# ProPrj.net
KiCad netlist of a schematic drawn in EasyEDA Pro
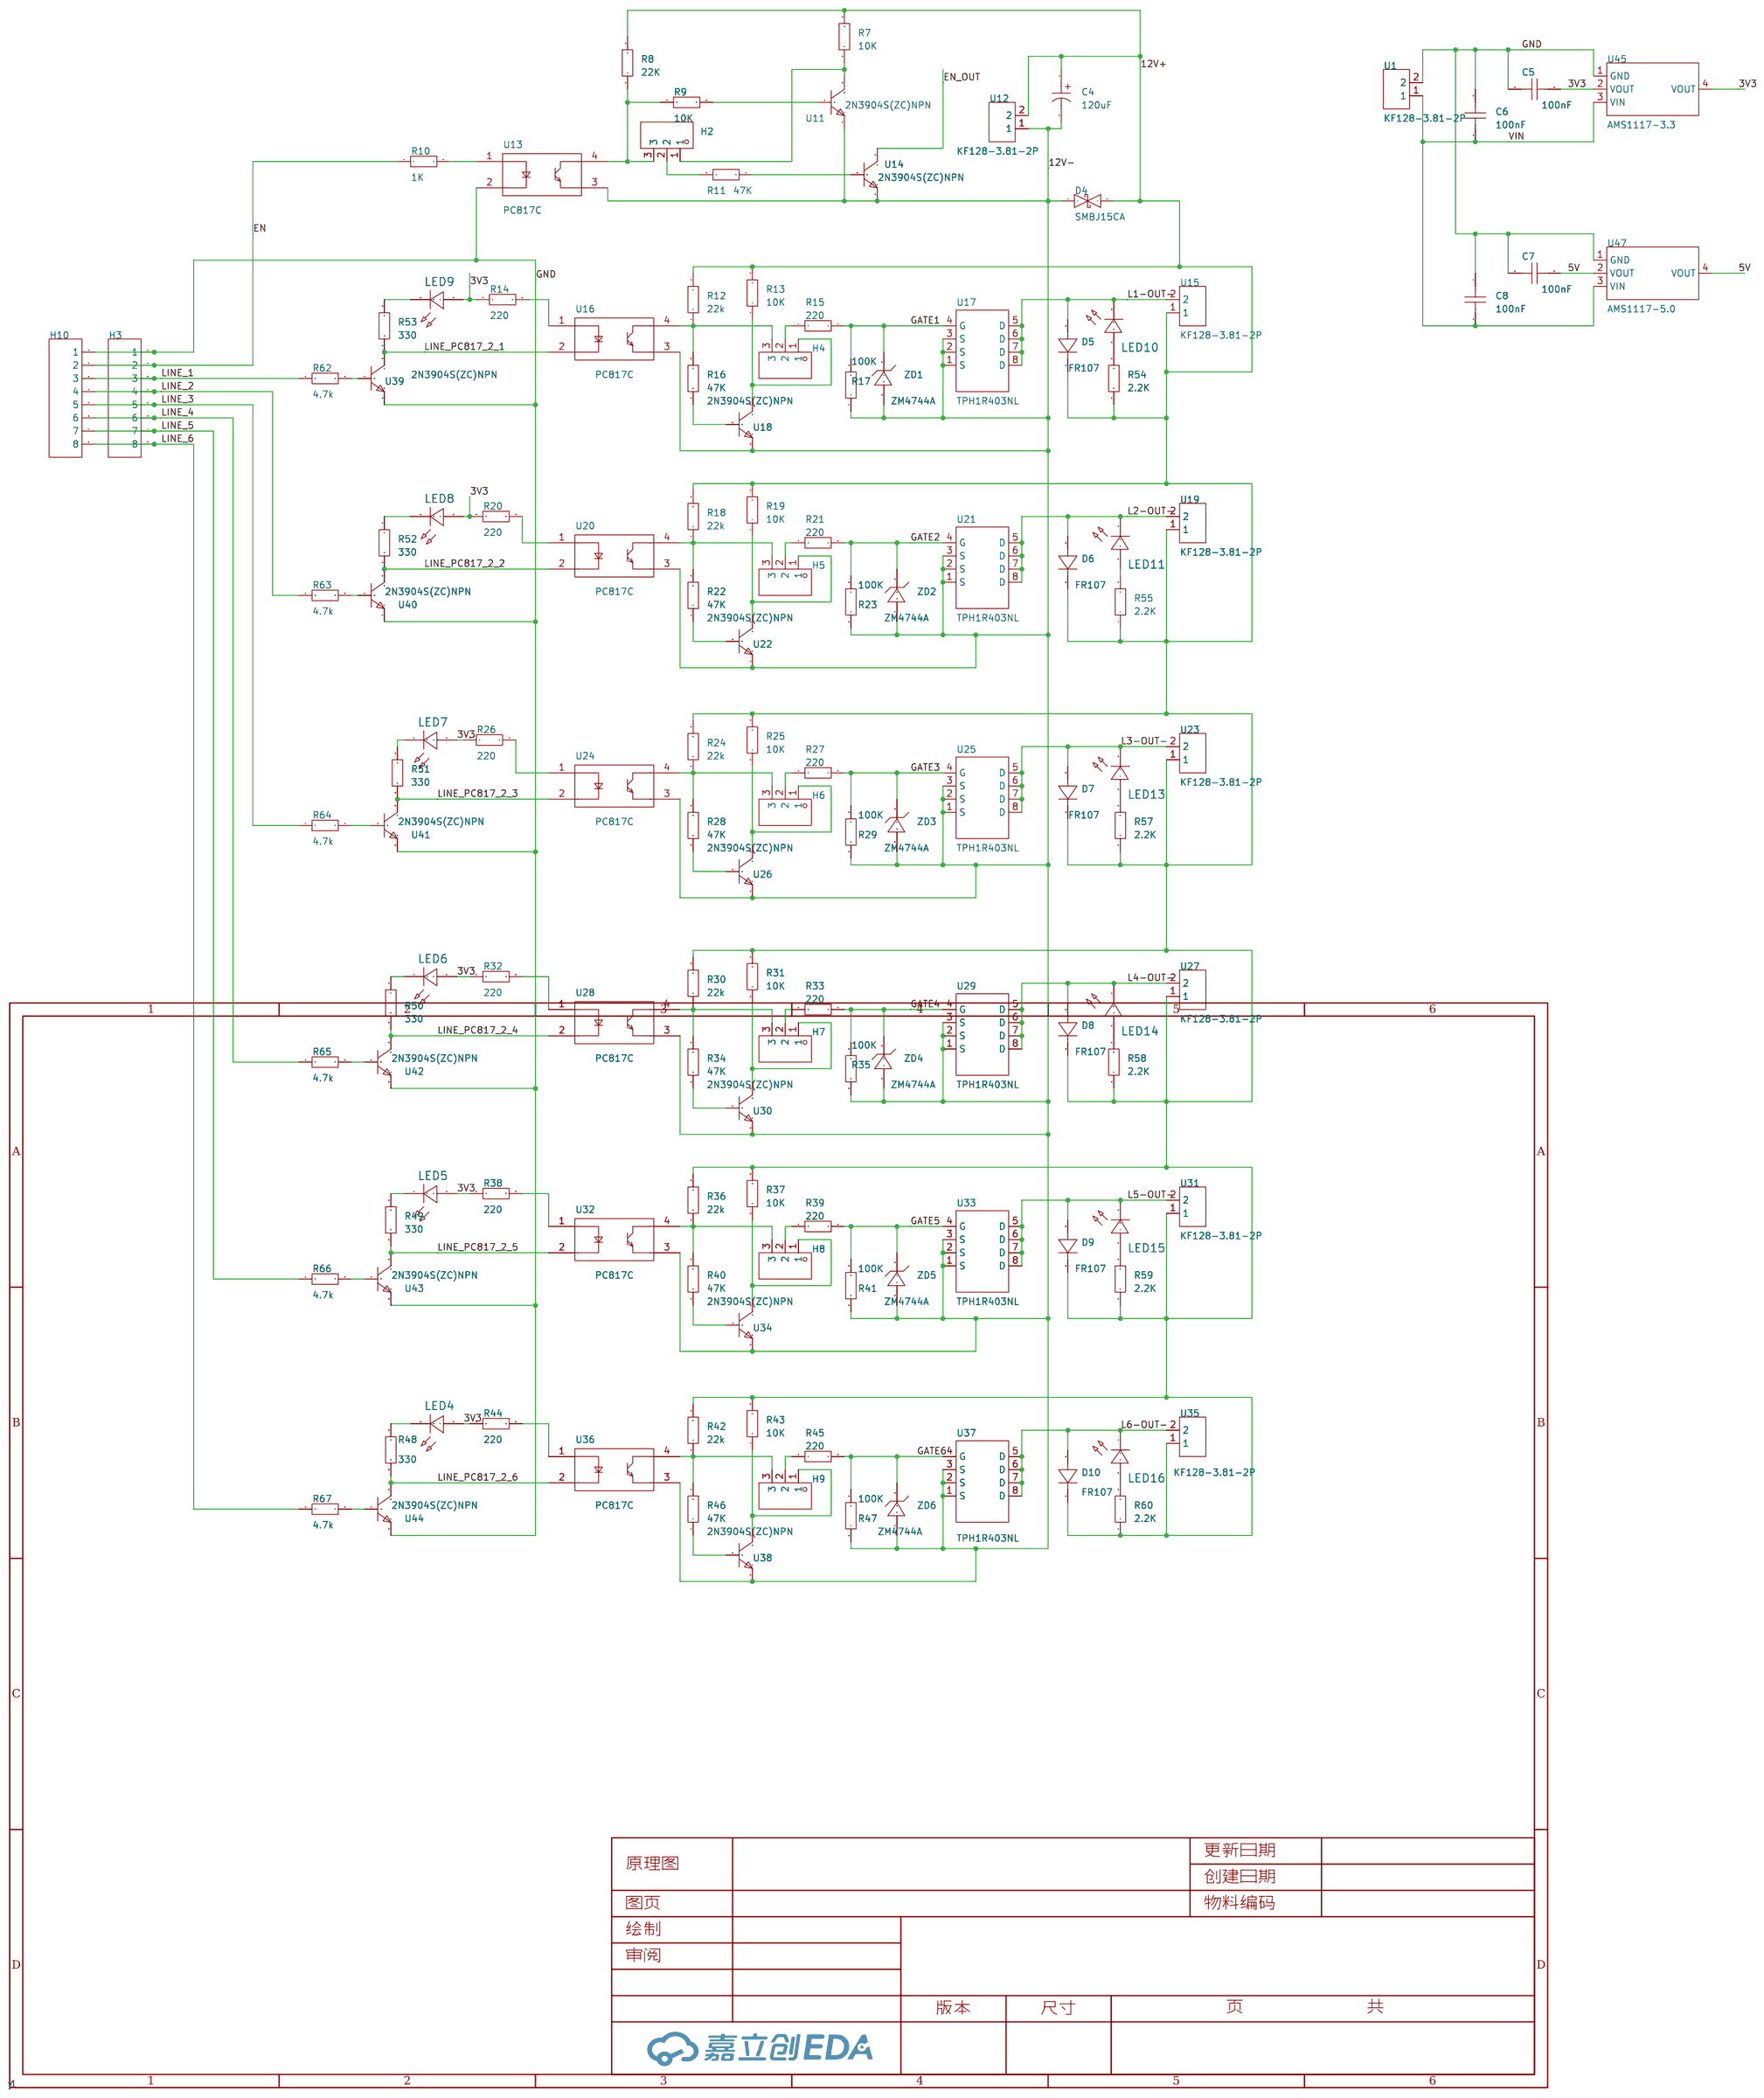
[diagram p0: 光耦隔离输出]
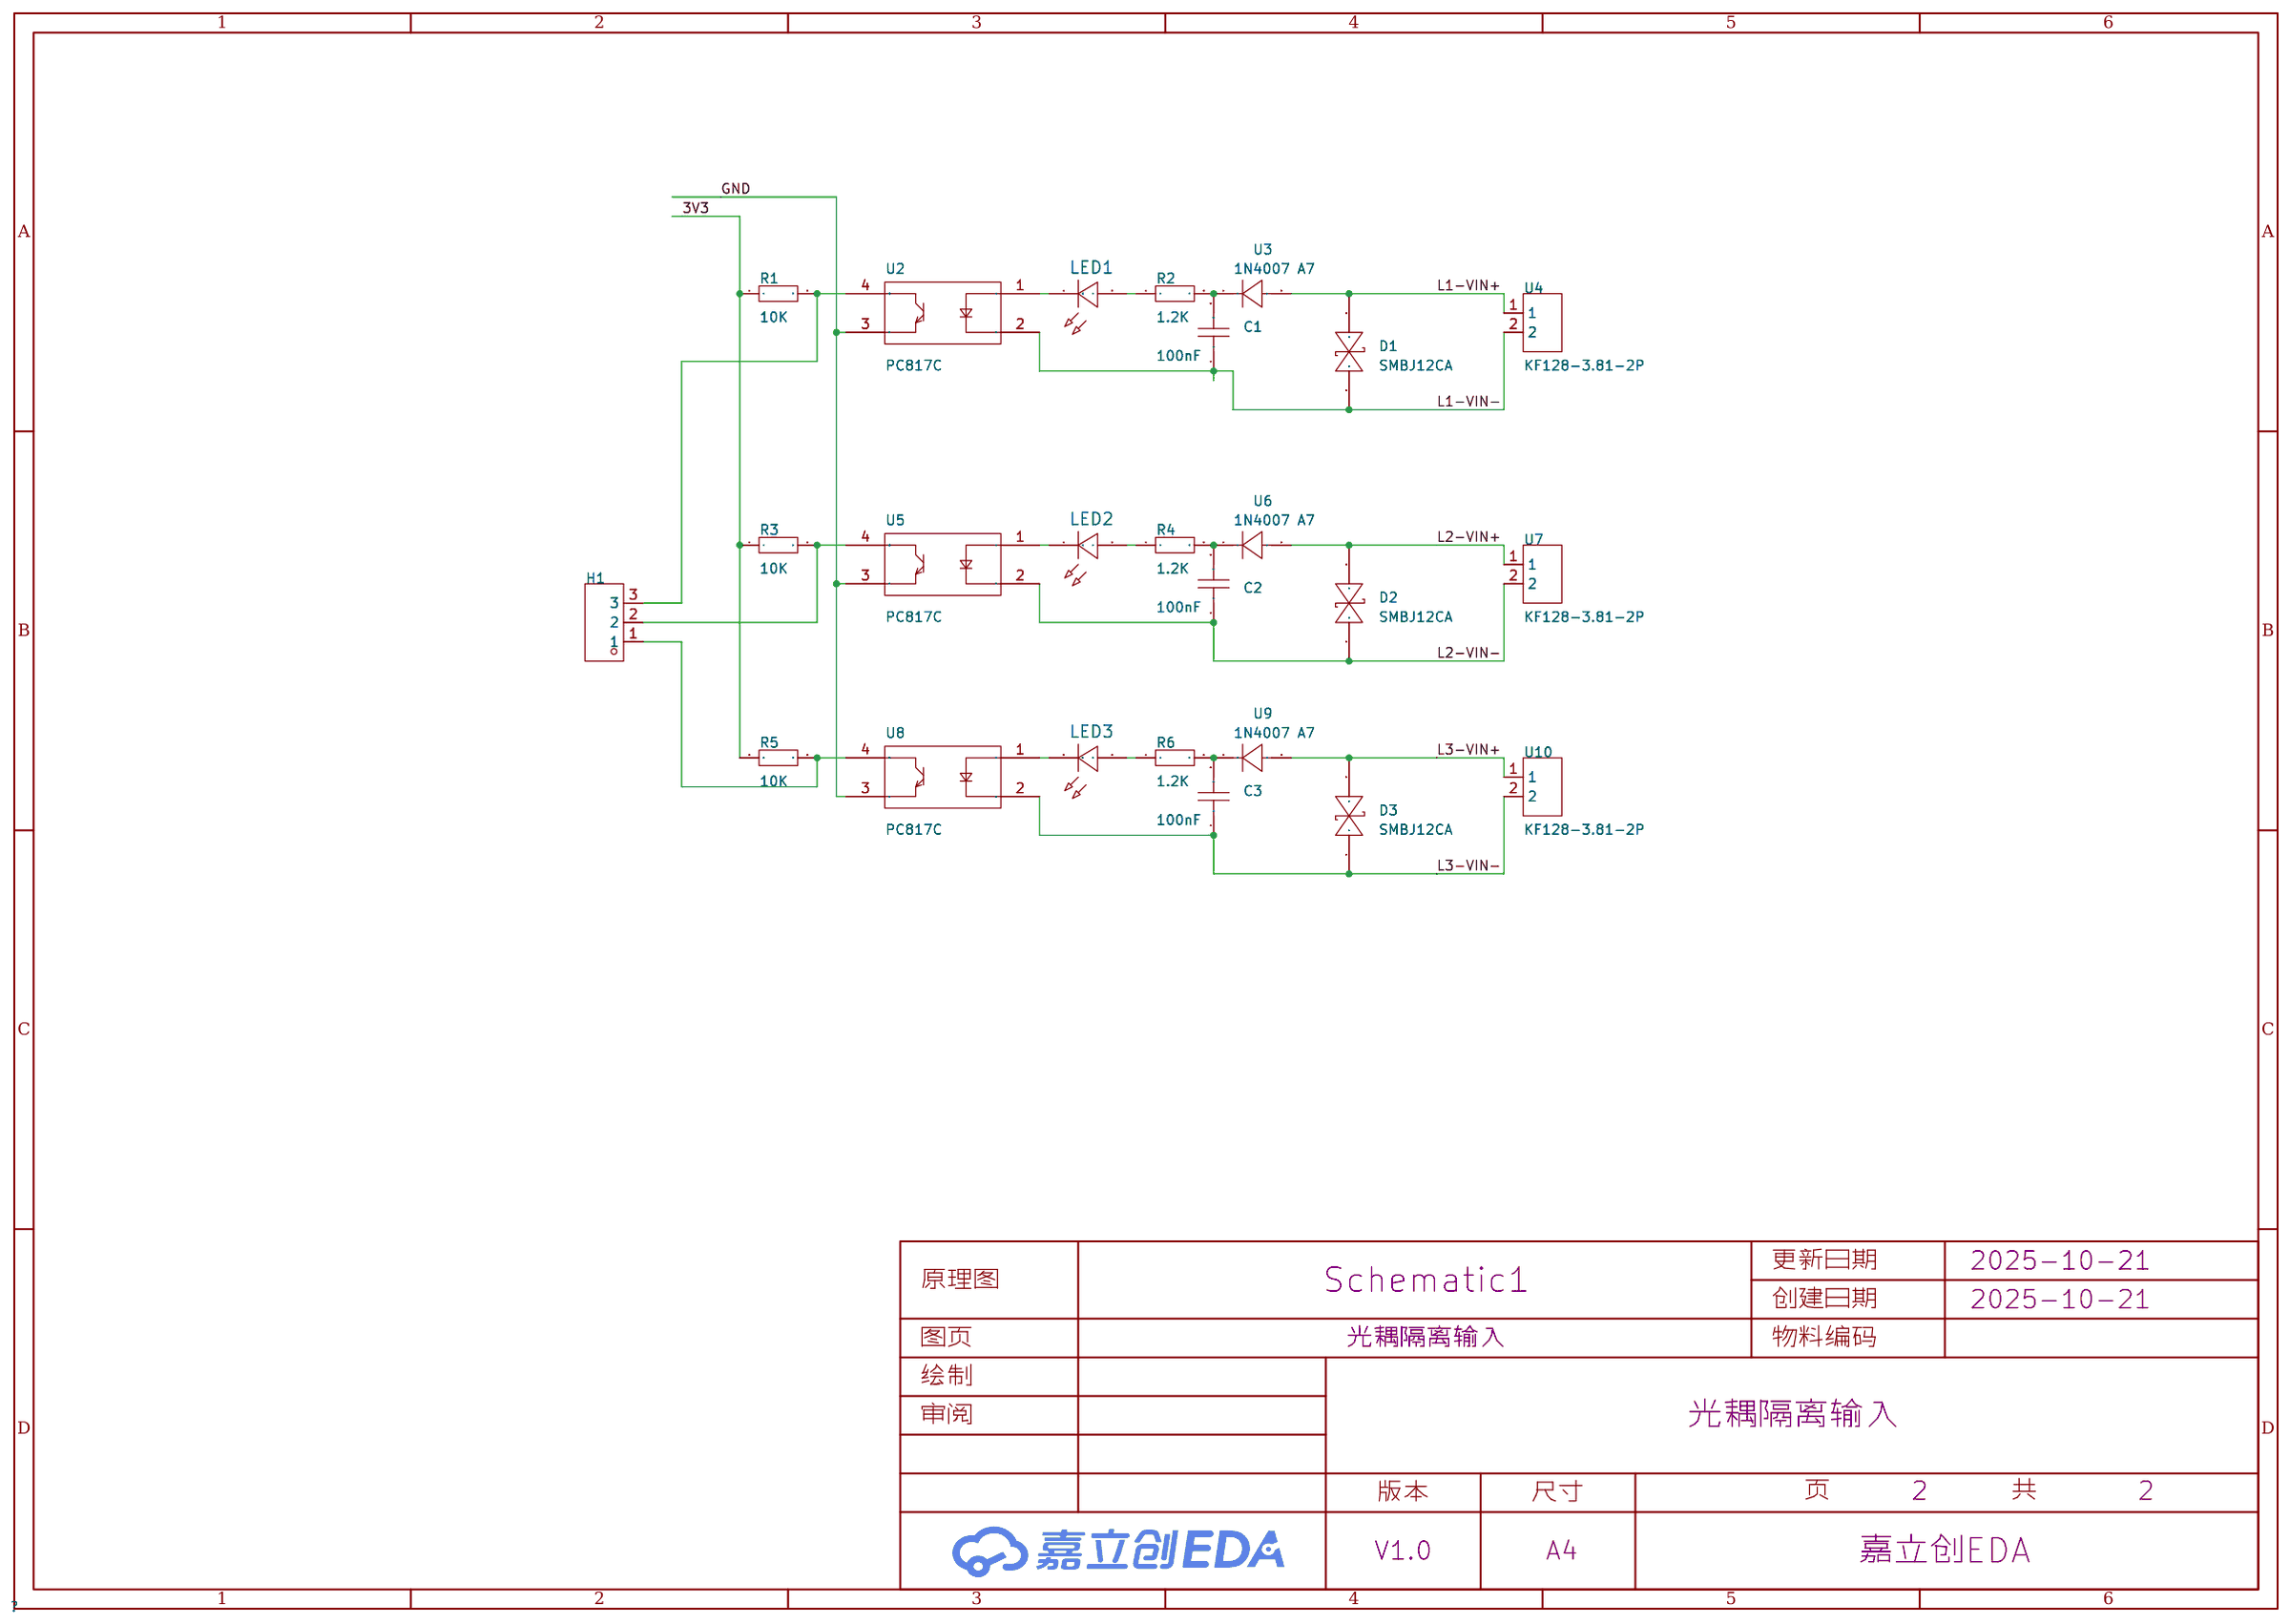
[diagram p1: 光耦隔离输入]

(export (version "E")
  (design (tool "Eeschema 10.0.6"))
  (components
    (comp (ref "C4")
      (value "120uF")
      (footprint "easyedapro:CAP-TH_BD6.3-P2.50-D0.5-FD")
      (description "容值:120uF;精度:±20%;额定电压:35V;纹波电流:550mA@100kHz;等效串联电阻(ESR):150mΩ@100kHz;")
      (fields
        (field (name "Manufacturer Part") "DHG035M127E090S1AA")
        (field (name "Manufacturer") "KNSCHA(科尼盛)")
      )
      (libsource (lib "easyedapro") (part "DHG035M127E090S1AA"))
    )
    (comp (ref "C5")
      (value "100nF")
      (footprint "easyedapro:C0603")
      (libsource (lib "easyedapro") (part "CapAcitance"))
    )
    (comp (ref "C6")
      (value "100nF")
      (footprint "easyedapro:C0603")
      (libsource (lib "easyedapro") (part "CapAcitance"))
    )
    (comp (ref "C7")
      (value "100nF")
      (footprint "easyedapro:C0603")
      (libsource (lib "easyedapro") (part "CapAcitance"))
    )
    (comp (ref "C8")
      (value "100nF")
      (footprint "easyedapro:C0603")
      (libsource (lib "easyedapro") (part "CapAcitance"))
    )
    (comp (ref "D4")
      (value "SMBJ15CA")
      (footprint "easyedapro:SMB_L4.6-W3.6-LS5.3-BI")
      (description "反向截止电压(Vrwm):15V;钳位电压:24.4V;峰值脉冲电流(Ipp):24.6A;击穿电压:16.7V;")
      (fields (field (name "Manufacturer") "JJW(捷捷微)"))
      (libsource (lib "easyedapro") (part "SMBJ15CA_C330064"))
    )
    (comp (ref "D5")
      (value "FR107")
      (footprint "easyedapro:SOD-123_L2.8-W1.8-LS3.7-RD")
      (description "二极管配置:-;正向压降(Vf):1.3V@1A;直流反向耐压(Vr):1kV;整流电流:1A;反向恢复时间(Trr):500ns;")
      (fields (field (name "Manufacturer") "JSMSEMI(杰盛微)"))
      (libsource (lib "easyedapro") (part "FR107_C963379"))
    )
    (comp (ref "D6")
      (value "FR107")
      (footprint "easyedapro:SOD-123_L2.8-W1.8-LS3.7-RD")
      (description "二极管配置:-;正向压降(Vf):1.3V@1A;直流反向耐压(Vr):1kV;整流电流:1A;反向恢复时间(Trr):500ns;")
      (fields (field (name "Manufacturer") "JSMSEMI(杰盛微)"))
      (libsource (lib "easyedapro") (part "FR107_C963379"))
    )
    (comp (ref "D7")
      (value "FR107")
      (footprint "easyedapro:SOD-123_L2.8-W1.8-LS3.7-RD")
      (description "二极管配置:-;正向压降(Vf):1.3V@1A;直流反向耐压(Vr):1kV;整流电流:1A;反向恢复时间(Trr):500ns;")
      (fields (field (name "Manufacturer") "JSMSEMI(杰盛微)"))
      (libsource (lib "easyedapro") (part "FR107_C963379"))
    )
    (comp (ref "D8")
      (value "FR107")
      (footprint "easyedapro:SOD-123_L2.8-W1.8-LS3.7-RD")
      (description "二极管配置:-;正向压降(Vf):1.3V@1A;直流反向耐压(Vr):1kV;整流电流:1A;反向恢复时间(Trr):500ns;")
      (fields (field (name "Manufacturer") "JSMSEMI(杰盛微)"))
      (libsource (lib "easyedapro") (part "FR107_C963379"))
    )
    (comp (ref "D9")
      (value "FR107")
      (footprint "easyedapro:SOD-123_L2.8-W1.8-LS3.7-RD")
      (description "二极管配置:-;正向压降(Vf):1.3V@1A;直流反向耐压(Vr):1kV;整流电流:1A;反向恢复时间(Trr):500ns;")
      (fields (field (name "Manufacturer") "JSMSEMI(杰盛微)"))
      (libsource (lib "easyedapro") (part "FR107_C963379"))
    )
    (comp (ref "D10")
      (value "FR107")
      (footprint "easyedapro:SOD-123_L2.8-W1.8-LS3.7-RD")
      (description "二极管配置:-;正向压降(Vf):1.3V@1A;直流反向耐压(Vr):1kV;整流电流:1A;反向恢复时间(Trr):500ns;")
      (fields (field (name "Manufacturer") "JSMSEMI(杰盛微)"))
      (libsource (lib "easyedapro") (part "FR107_C963379"))
    )
    (comp (ref "H2")
      (value "~")
      (footprint "easyedapro:HDR-TH_3P-P2.54-V-M")
      (libsource (lib "easyedapro") (part "HDR-M_2.54_1x3P"))
    )
    (comp (ref "H3")
      (value "~")
      (footprint "easyedapro:HDR-TH_8P-P2.54-V-M")
      (libsource (lib "easyedapro") (part "Header-Male-2.54_1x8"))
    )
    (comp (ref "H4")
      (value "~")
      (footprint "easyedapro:HDR-TH_3P-P2.54-V-M")
      (libsource (lib "easyedapro") (part "HDR-M_2.54_1x3P"))
    )
    (comp (ref "H5")
      (value "~")
      (footprint "easyedapro:HDR-TH_3P-P2.54-V-M")
      (libsource (lib "easyedapro") (part "HDR-M_2.54_1x3P"))
    )
    (comp (ref "H6")
      (value "~")
      (footprint "easyedapro:HDR-TH_3P-P2.54-V-M")
      (libsource (lib "easyedapro") (part "HDR-M_2.54_1x3P"))
    )
    (comp (ref "H7")
      (value "~")
      (footprint "easyedapro:HDR-TH_3P-P2.54-V-M")
      (libsource (lib "easyedapro") (part "HDR-M_2.54_1x3P"))
    )
    (comp (ref "H8")
      (value "~")
      (footprint "easyedapro:HDR-TH_3P-P2.54-V-M")
      (libsource (lib "easyedapro") (part "HDR-M_2.54_1x3P"))
    )
    (comp (ref "H9")
      (value "~")
      (footprint "easyedapro:HDR-TH_3P-P2.54-V-M")
      (libsource (lib "easyedapro") (part "HDR-M_2.54_1x3P"))
    )
    (comp (ref "H10")
      (value "~")
      (footprint "easyedapro:HDR-TH_8P-P2.54-V-M")
      (libsource (lib "easyedapro") (part "Header-Male-2.54_1x8"))
    )
    (comp (ref "LED4")
      (value "~")
      (footprint "easyedapro:LED_0603")
      (libsource (lib "easyedapro") (part "LED_R"))
    )
    (comp (ref "LED5")
      (value "~")
      (footprint "easyedapro:LED_0603")
      (libsource (lib "easyedapro") (part "LED_R"))
    )
    (comp (ref "LED6")
      (value "~")
      (footprint "easyedapro:LED_0603")
      (libsource (lib "easyedapro") (part "LED_R"))
    )
    (comp (ref "LED7")
      (value "~")
      (footprint "easyedapro:LED_0603")
      (libsource (lib "easyedapro") (part "LED_R"))
    )
    (comp (ref "LED8")
      (value "~")
      (footprint "easyedapro:LED_0603")
      (libsource (lib "easyedapro") (part "LED_R"))
    )
    (comp (ref "LED9")
      (value "~")
      (footprint "easyedapro:LED_0603")
      (libsource (lib "easyedapro") (part "LED_R"))
    )
    (comp (ref "LED10")
      (value "~")
      (footprint "easyedapro:LED_0603")
      (libsource (lib "easyedapro") (part "LED_R"))
    )
    (comp (ref "LED11")
      (value "~")
      (footprint "easyedapro:LED_0603")
      (libsource (lib "easyedapro") (part "LED_R"))
    )
    (comp (ref "LED13")
      (value "~")
      (footprint "easyedapro:LED_0603")
      (libsource (lib "easyedapro") (part "LED_R"))
    )
    (comp (ref "LED14")
      (value "~")
      (footprint "easyedapro:LED_0603")
      (libsource (lib "easyedapro") (part "LED_R"))
    )
    (comp (ref "LED15")
      (value "~")
      (footprint "easyedapro:LED_0603")
      (libsource (lib "easyedapro") (part "LED_R"))
    )
    (comp (ref "LED16")
      (value "~")
      (footprint "easyedapro:LED_0603")
      (libsource (lib "easyedapro") (part "LED_R"))
    )
    (comp (ref "R7") (value "10K") (footprint "easyedapro:R0603") (libsource (lib "easyedapro") (part "电阻")))
    (comp (ref "R8") (value "22K") (footprint "easyedapro:R0603") (libsource (lib "easyedapro") (part "电阻")))
    (comp (ref "R9") (value "10K") (footprint "easyedapro:R0603") (libsource (lib "easyedapro") (part "电阻")))
    (comp (ref "R10") (value "1K") (footprint "easyedapro:R0603") (libsource (lib "easyedapro") (part "电阻")))
    (comp (ref "R11") (value "47K") (footprint "easyedapro:R0603") (libsource (lib "easyedapro") (part "电阻")))
    (comp (ref "R12") (value "22k") (footprint "easyedapro:R0603") (libsource (lib "easyedapro") (part "电阻")))
    (comp (ref "R13") (value "10K") (footprint "easyedapro:R0603") (libsource (lib "easyedapro") (part "电阻")))
    (comp (ref "R14") (value "220") (footprint "easyedapro:R0603") (libsource (lib "easyedapro") (part "电阻")))
    (comp (ref "R15") (value "220") (footprint "easyedapro:R0603") (libsource (lib "easyedapro") (part "电阻")))
    (comp (ref "R16") (value "47K") (footprint "easyedapro:R0603") (libsource (lib "easyedapro") (part "电阻")))
    (comp (ref "R17")
      (value "100K")
      (footprint "easyedapro:R0603")
      (libsource (lib "easyedapro") (part "电阻"))
    )
    (comp (ref "R18") (value "22k") (footprint "easyedapro:R0603") (libsource (lib "easyedapro") (part "电阻")))
    (comp (ref "R19") (value "10K") (footprint "easyedapro:R0603") (libsource (lib "easyedapro") (part "电阻")))
    (comp (ref "R20") (value "220") (footprint "easyedapro:R0603") (libsource (lib "easyedapro") (part "电阻")))
    (comp (ref "R21") (value "220") (footprint "easyedapro:R0603") (libsource (lib "easyedapro") (part "电阻")))
    (comp (ref "R22") (value "47K") (footprint "easyedapro:R0603") (libsource (lib "easyedapro") (part "电阻")))
    (comp (ref "R23")
      (value "100K")
      (footprint "easyedapro:R0603")
      (libsource (lib "easyedapro") (part "电阻"))
    )
    (comp (ref "R24") (value "22k") (footprint "easyedapro:R0603") (libsource (lib "easyedapro") (part "电阻")))
    (comp (ref "R25") (value "10K") (footprint "easyedapro:R0603") (libsource (lib "easyedapro") (part "电阻")))
    (comp (ref "R26") (value "220") (footprint "easyedapro:R0603") (libsource (lib "easyedapro") (part "电阻")))
    (comp (ref "R27") (value "220") (footprint "easyedapro:R0603") (libsource (lib "easyedapro") (part "电阻")))
    (comp (ref "R28") (value "47K") (footprint "easyedapro:R0603") (libsource (lib "easyedapro") (part "电阻")))
    (comp (ref "R29")
      (value "100K")
      (footprint "easyedapro:R0603")
      (libsource (lib "easyedapro") (part "电阻"))
    )
    (comp (ref "R30") (value "22k") (footprint "easyedapro:R0603") (libsource (lib "easyedapro") (part "电阻")))
    (comp (ref "R31") (value "10K") (footprint "easyedapro:R0603") (libsource (lib "easyedapro") (part "电阻")))
    (comp (ref "R32") (value "220") (footprint "easyedapro:R0603") (libsource (lib "easyedapro") (part "电阻")))
    (comp (ref "R33") (value "220") (footprint "easyedapro:R0603") (libsource (lib "easyedapro") (part "电阻")))
    (comp (ref "R34") (value "47K") (footprint "easyedapro:R0603") (libsource (lib "easyedapro") (part "电阻")))
    (comp (ref "R35")
      (value "100K")
      (footprint "easyedapro:R0603")
      (libsource (lib "easyedapro") (part "电阻"))
    )
    (comp (ref "R36") (value "22k") (footprint "easyedapro:R0603") (libsource (lib "easyedapro") (part "电阻")))
    (comp (ref "R37") (value "10K") (footprint "easyedapro:R0603") (libsource (lib "easyedapro") (part "电阻")))
    (comp (ref "R38") (value "220") (footprint "easyedapro:R0603") (libsource (lib "easyedapro") (part "电阻")))
    (comp (ref "R39") (value "220") (footprint "easyedapro:R0603") (libsource (lib "easyedapro") (part "电阻")))
    (comp (ref "R40") (value "47K") (footprint "easyedapro:R0603") (libsource (lib "easyedapro") (part "电阻")))
    (comp (ref "R41")
      (value "100K")
      (footprint "easyedapro:R0603")
      (libsource (lib "easyedapro") (part "电阻"))
    )
    (comp (ref "R42") (value "22k") (footprint "easyedapro:R0603") (libsource (lib "easyedapro") (part "电阻")))
    (comp (ref "R43") (value "10K") (footprint "easyedapro:R0603") (libsource (lib "easyedapro") (part "电阻")))
    (comp (ref "R44") (value "220") (footprint "easyedapro:R0603") (libsource (lib "easyedapro") (part "电阻")))
    (comp (ref "R45") (value "220") (footprint "easyedapro:R0603") (libsource (lib "easyedapro") (part "电阻")))
    (comp (ref "R46") (value "47K") (footprint "easyedapro:R0603") (libsource (lib "easyedapro") (part "电阻")))
    (comp (ref "R47")
      (value "100K")
      (footprint "easyedapro:R0603")
      (libsource (lib "easyedapro") (part "电阻"))
    )
    (comp (ref "R48") (value "330") (footprint "easyedapro:R0603") (libsource (lib "easyedapro") (part "电阻")))
    (comp (ref "R49") (value "330") (footprint "easyedapro:R0603") (libsource (lib "easyedapro") (part "电阻")))
    (comp (ref "R50") (value "330") (footprint "easyedapro:R0603") (libsource (lib "easyedapro") (part "电阻")))
    (comp (ref "R51") (value "330") (footprint "easyedapro:R0603") (libsource (lib "easyedapro") (part "电阻")))
    (comp (ref "R52") (value "330") (footprint "easyedapro:R0603") (libsource (lib "easyedapro") (part "电阻")))
    (comp (ref "R53") (value "330") (footprint "easyedapro:R0603") (libsource (lib "easyedapro") (part "电阻")))
    (comp (ref "R54")
      (value "2.2K")
      (footprint "easyedapro:R0603")
      (libsource (lib "easyedapro") (part "电阻"))
    )
    (comp (ref "R55")
      (value "2.2K")
      (footprint "easyedapro:R0603")
      (libsource (lib "easyedapro") (part "电阻"))
    )
    (comp (ref "R57")
      (value "2.2K")
      (footprint "easyedapro:R0603")
      (libsource (lib "easyedapro") (part "电阻"))
    )
    (comp (ref "R58")
      (value "2.2K")
      (footprint "easyedapro:R0603")
      (libsource (lib "easyedapro") (part "电阻"))
    )
    (comp (ref "R59")
      (value "2.2K")
      (footprint "easyedapro:R0603")
      (libsource (lib "easyedapro") (part "电阻"))
    )
    (comp (ref "R60")
      (value "2.2K")
      (footprint "easyedapro:R0603")
      (libsource (lib "easyedapro") (part "电阻"))
    )
    (comp (ref "R62")
      (value "4.7k")
      (footprint "easyedapro:R0603")
      (libsource (lib "easyedapro") (part "电阻"))
    )
    (comp (ref "R63")
      (value "4.7k")
      (footprint "easyedapro:R0603")
      (libsource (lib "easyedapro") (part "电阻"))
    )
    (comp (ref "R64")
      (value "4.7k")
      (footprint "easyedapro:R0603")
      (libsource (lib "easyedapro") (part "电阻"))
    )
    (comp (ref "R65")
      (value "4.7k")
      (footprint "easyedapro:R0603")
      (libsource (lib "easyedapro") (part "电阻"))
    )
    (comp (ref "R66")
      (value "4.7k")
      (footprint "easyedapro:R0603")
      (libsource (lib "easyedapro") (part "电阻"))
    )
    (comp (ref "R67")
      (value "4.7k")
      (footprint "easyedapro:R0603")
      (libsource (lib "easyedapro") (part "电阻"))
    )
    (comp (ref "U1")
      (value "KF128-3.81-2P")
      (footprint "easyedapro:CONN-TH_2P-P3.81_KF128-3.81-2P")
      (libsource (lib "easyedapro") (part "KF128-3.81-2P_C9900030554"))
    )
    (comp (ref "U11")
      (value "2N3904S(ZC)NPN")
      (footprint "easyedapro:SOT-23-3_L2.9-W1.3-P0.95-LS2.4-BR")
      (libsource (lib "easyedapro") (part "2N3904S(ZC)NPN"))
    )
    (comp (ref "U12")
      (value "KF128-3.81-2P")
      (footprint "easyedapro:CONN-TH_2P-P3.81_KF128-3.81-2P")
      (libsource (lib "easyedapro") (part "KF128-3.81-2P_C9900030554"))
    )
    (comp (ref "U13")
      (value "PC817C")
      (footprint "easyedapro:DIP-4_L4.6-W6.5-P2.54-LS7.6-BL")
      (fields (field (name "Manufacturer") "GOODWORK(固得沃克)"))
      (libsource (lib "easyedapro") (part "PC817-4"))
    )
    (comp (ref "U14")
      (value "2N3904S(ZC)NPN")
      (footprint "easyedapro:SOT-23-3_L2.9-W1.3-P0.95-LS2.4-BR")
      (libsource (lib "easyedapro") (part "2N3904S(ZC)NPN"))
    )
    (comp (ref "U15")
      (value "KF128-3.81-2P")
      (footprint "easyedapro:CONN-TH_2P-P3.81_KF128-3.81-2P")
      (libsource (lib "easyedapro") (part "KF128-3.81-2P_C9900030554"))
    )
    (comp (ref "U16")
      (value "PC817C")
      (footprint "easyedapro:DIP-4_L4.6-W6.5-P2.54-LS7.6-BL")
      (fields (field (name "Manufacturer") "GOODWORK(固得沃克)"))
      (libsource (lib "easyedapro") (part "PC817-4"))
    )
    (comp (ref "U17")
      (value "TPH1R403NL")
      (footprint "easyedapro:DFN-8_L5.0-W5.0-P1.27-LS6.0-EP")
      (libsource (lib "easyedapro") (part "TPH1R403NL_C9900016373"))
    )
    (comp (ref "U18")
      (value "2N3904S(ZC)NPN")
      (footprint "easyedapro:SOT-23-3_L2.9-W1.3-P0.95-LS2.4-BR")
      (libsource (lib "easyedapro") (part "2N3904S(ZC)NPN"))
    )
    (comp (ref "U19")
      (value "KF128-3.81-2P")
      (footprint "easyedapro:CONN-TH_2P-P3.81_KF128-3.81-2P")
      (libsource (lib "easyedapro") (part "KF128-3.81-2P_C9900030554"))
    )
    (comp (ref "U20")
      (value "PC817C")
      (footprint "easyedapro:DIP-4_L4.6-W6.5-P2.54-LS7.6-BL")
      (fields (field (name "Manufacturer") "GOODWORK(固得沃克)"))
      (libsource (lib "easyedapro") (part "PC817-4"))
    )
    (comp (ref "U21")
      (value "TPH1R403NL")
      (footprint "easyedapro:DFN-8_L5.0-W5.0-P1.27-LS6.0-EP")
      (libsource (lib "easyedapro") (part "TPH1R403NL_C9900016373"))
    )
    (comp (ref "U22")
      (value "2N3904S(ZC)NPN")
      (footprint "easyedapro:SOT-23-3_L2.9-W1.3-P0.95-LS2.4-BR")
      (libsource (lib "easyedapro") (part "2N3904S(ZC)NPN"))
    )
    (comp (ref "U23")
      (value "KF128-3.81-2P")
      (footprint "easyedapro:CONN-TH_2P-P3.81_KF128-3.81-2P")
      (libsource (lib "easyedapro") (part "KF128-3.81-2P_C9900030554"))
    )
    (comp (ref "U24")
      (value "PC817C")
      (footprint "easyedapro:DIP-4_L4.6-W6.5-P2.54-LS7.6-BL")
      (fields (field (name "Manufacturer") "GOODWORK(固得沃克)"))
      (libsource (lib "easyedapro") (part "PC817-4"))
    )
    (comp (ref "U25")
      (value "TPH1R403NL")
      (footprint "easyedapro:DFN-8_L5.0-W5.0-P1.27-LS6.0-EP")
      (libsource (lib "easyedapro") (part "TPH1R403NL_C9900016373"))
    )
    (comp (ref "U26")
      (value "2N3904S(ZC)NPN")
      (footprint "easyedapro:SOT-23-3_L2.9-W1.3-P0.95-LS2.4-BR")
      (libsource (lib "easyedapro") (part "2N3904S(ZC)NPN"))
    )
    (comp (ref "U27")
      (value "KF128-3.81-2P")
      (footprint "easyedapro:CONN-TH_2P-P3.81_KF128-3.81-2P")
      (libsource (lib "easyedapro") (part "KF128-3.81-2P_C9900030554"))
    )
    (comp (ref "U28")
      (value "PC817C")
      (footprint "easyedapro:DIP-4_L4.6-W6.5-P2.54-LS7.6-BL")
      (fields (field (name "Manufacturer") "GOODWORK(固得沃克)"))
      (libsource (lib "easyedapro") (part "PC817-4"))
    )
    (comp (ref "U29")
      (value "TPH1R403NL")
      (footprint "easyedapro:DFN-8_L5.0-W5.0-P1.27-LS6.0-EP")
      (libsource (lib "easyedapro") (part "TPH1R403NL_C9900016373"))
    )
    (comp (ref "U30")
      (value "2N3904S(ZC)NPN")
      (footprint "easyedapro:SOT-23-3_L2.9-W1.3-P0.95-LS2.4-BR")
      (libsource (lib "easyedapro") (part "2N3904S(ZC)NPN"))
    )
    (comp (ref "U31")
      (value "KF128-3.81-2P")
      (footprint "easyedapro:CONN-TH_2P-P3.81_KF128-3.81-2P")
      (libsource (lib "easyedapro") (part "KF128-3.81-2P_C9900030554"))
    )
    (comp (ref "U32")
      (value "PC817C")
      (footprint "easyedapro:DIP-4_L4.6-W6.5-P2.54-LS7.6-BL")
      (fields (field (name "Manufacturer") "GOODWORK(固得沃克)"))
      (libsource (lib "easyedapro") (part "PC817-4"))
    )
    (comp (ref "U33")
      (value "TPH1R403NL")
      (footprint "easyedapro:DFN-8_L5.0-W5.0-P1.27-LS6.0-EP")
      (libsource (lib "easyedapro") (part "TPH1R403NL_C9900016373"))
    )
    (comp (ref "U34")
      (value "2N3904S(ZC)NPN")
      (footprint "easyedapro:SOT-23-3_L2.9-W1.3-P0.95-LS2.4-BR")
      (libsource (lib "easyedapro") (part "2N3904S(ZC)NPN"))
    )
    (comp (ref "U35")
      (value "KF128-3.81-2P")
      (footprint "easyedapro:CONN-TH_2P-P3.81_KF128-3.81-2P")
      (libsource (lib "easyedapro") (part "KF128-3.81-2P_C9900030554"))
    )
    (comp (ref "U36")
      (value "PC817C")
      (footprint "easyedapro:DIP-4_L4.6-W6.5-P2.54-LS7.6-BL")
      (fields (field (name "Manufacturer") "GOODWORK(固得沃克)"))
      (libsource (lib "easyedapro") (part "PC817-4"))
    )
    (comp (ref "U37")
      (value "TPH1R403NL")
      (footprint "easyedapro:DFN-8_L5.0-W5.0-P1.27-LS6.0-EP")
      (libsource (lib "easyedapro") (part "TPH1R403NL_C9900016373"))
    )
    (comp (ref "U38")
      (value "2N3904S(ZC)NPN")
      (footprint "easyedapro:SOT-23-3_L2.9-W1.3-P0.95-LS2.4-BR")
      (libsource (lib "easyedapro") (part "2N3904S(ZC)NPN"))
    )
    (comp (ref "U39")
      (value "2N3904S(ZC)NPN")
      (footprint "easyedapro:SOT-23-3_L2.9-W1.3-P0.95-LS2.4-BR")
      (libsource (lib "easyedapro") (part "2N3904S(ZC)NPN"))
    )
    (comp (ref "U40")
      (value "2N3904S(ZC)NPN")
      (footprint "easyedapro:SOT-23-3_L2.9-W1.3-P0.95-LS2.4-BR")
      (libsource (lib "easyedapro") (part "2N3904S(ZC)NPN"))
    )
    (comp (ref "U41")
      (value "2N3904S(ZC)NPN")
      (footprint "easyedapro:SOT-23-3_L2.9-W1.3-P0.95-LS2.4-BR")
      (libsource (lib "easyedapro") (part "2N3904S(ZC)NPN"))
    )
    (comp (ref "U42")
      (value "2N3904S(ZC)NPN")
      (footprint "easyedapro:SOT-23-3_L2.9-W1.3-P0.95-LS2.4-BR")
      (libsource (lib "easyedapro") (part "2N3904S(ZC)NPN"))
    )
    (comp (ref "U43")
      (value "2N3904S(ZC)NPN")
      (footprint "easyedapro:SOT-23-3_L2.9-W1.3-P0.95-LS2.4-BR")
      (libsource (lib "easyedapro") (part "2N3904S(ZC)NPN"))
    )
    (comp (ref "U44")
      (value "2N3904S(ZC)NPN")
      (footprint "easyedapro:SOT-23-3_L2.9-W1.3-P0.95-LS2.4-BR")
      (libsource (lib "easyedapro") (part "2N3904S(ZC)NPN"))
    )
    (comp (ref "U45")
      (value "AMS1117-3.3")
      (footprint "easyedapro:SOT-223-3_L6.5-W3.4-P2.30-LS7.0-BR")
      (description "输出类型:固定;工作电压:16V;输出电压:3.3V;输出电流:1A;电源纹波抑制比(PSRR):72dB@(120Hz);输出极性:正极;")
      (fields (field (name "Manufacturer") "AMS"))
      (libsource (lib "easyedapro") (part "AMS1117-3.3"))
    )
    (comp (ref "U47")
      (value "AMS1117-5.0")
      (footprint "easyedapro:SOT-223_L6.5-W3.5-P2.30-LS7.0-BR")
      (description "输出类型:固定;工作电压:15V;输出电压:5V;输出电流:1A;电源纹波抑制比(PSRR):60dB;输出极性:正极;")
      (fields (field (name "Manufacturer") "AMS"))
      (libsource (lib "easyedapro") (part "AMS1117-5.0"))
    )
    (comp (ref "ZD1")
      (value "ZM4744A")
      (footprint "easyedapro:LL-41_L5.0-W2.5-LS5.0-RD")
      (description "二极管配置:独立式;稳压值(标称值):15V;耗散功率(Pd):1W;")
      (fields (field (name "Manufacturer") "ST(先科)"))
      (libsource (lib "easyedapro") (part "ZM4744A"))
    )
    (comp (ref "ZD2")
      (value "ZM4744A")
      (footprint "easyedapro:LL-41_L5.0-W2.5-LS5.0-RD")
      (description "二极管配置:独立式;稳压值(标称值):15V;耗散功率(Pd):1W;")
      (fields (field (name "Manufacturer") "ST(先科)"))
      (libsource (lib "easyedapro") (part "ZM4744A"))
    )
    (comp (ref "ZD3")
      (value "ZM4744A")
      (footprint "easyedapro:LL-41_L5.0-W2.5-LS5.0-RD")
      (description "二极管配置:独立式;稳压值(标称值):15V;耗散功率(Pd):1W;")
      (fields (field (name "Manufacturer") "ST(先科)"))
      (libsource (lib "easyedapro") (part "ZM4744A"))
    )
    (comp (ref "ZD4")
      (value "ZM4744A")
      (footprint "easyedapro:LL-41_L5.0-W2.5-LS5.0-RD")
      (description "二极管配置:独立式;稳压值(标称值):15V;耗散功率(Pd):1W;")
      (fields (field (name "Manufacturer") "ST(先科)"))
      (libsource (lib "easyedapro") (part "ZM4744A"))
    )
    (comp (ref "ZD5")
      (value "ZM4744A")
      (footprint "easyedapro:LL-41_L5.0-W2.5-LS5.0-RD")
      (description "二极管配置:独立式;稳压值(标称值):15V;耗散功率(Pd):1W;")
      (fields (field (name "Manufacturer") "ST(先科)"))
      (libsource (lib "easyedapro") (part "ZM4744A"))
    )
    (comp (ref "ZD6")
      (value "ZM4744A")
      (footprint "easyedapro:LL-41_L5.0-W2.5-LS5.0-RD")
      (description "二极管配置:独立式;稳压值(标称值):15V;耗散功率(Pd):1W;")
      (fields (field (name "Manufacturer") "ST(先科)"))
      (libsource (lib "easyedapro") (part "ZM4744A"))
    )
    (comp (ref "C1")
      (value "100nF")
      (footprint "easyedapro:C0603")
      (libsource (lib "easyedapro") (part "CapAcitance"))
    )
    (comp (ref "C2")
      (value "100nF")
      (footprint "easyedapro:C0603")
      (libsource (lib "easyedapro") (part "CapAcitance"))
    )
    (comp (ref "C3")
      (value "100nF")
      (footprint "easyedapro:C0603")
      (libsource (lib "easyedapro") (part "CapAcitance"))
    )
    (comp (ref "D1")
      (value "SMBJ12CA")
      (footprint "easyedapro:SMB_L4.6-W3.6-LS5.3-BI")
      (description "反向截止电压(Vrwm):12V;最大钳位电压:19.9V;峰值脉冲电流(Ipp):30.2A;击穿电压:13.3V;")
      (fields (field (name "Manufacturer") "FMS(美丽微)"))
      (libsource (lib "easyedapro") (part "SMBJ12CA_C143145"))
    )
    (comp (ref "D2")
      (value "SMBJ12CA")
      (footprint "easyedapro:SMB_L4.6-W3.6-LS5.3-BI")
      (description "反向截止电压(Vrwm):12V;最大钳位电压:19.9V;峰值脉冲电流(Ipp):30.2A;击穿电压:13.3V;")
      (fields (field (name "Manufacturer") "FMS(美丽微)"))
      (libsource (lib "easyedapro") (part "SMBJ12CA_C143145"))
    )
    (comp (ref "D3")
      (value "SMBJ12CA")
      (footprint "easyedapro:SMB_L4.6-W3.6-LS5.3-BI")
      (description "反向截止电压(Vrwm):12V;最大钳位电压:19.9V;峰值脉冲电流(Ipp):30.2A;击穿电压:13.3V;")
      (fields (field (name "Manufacturer") "FMS(美丽微)"))
      (libsource (lib "easyedapro") (part "SMBJ12CA_C143145"))
    )
    (comp (ref "H1")
      (value "~")
      (footprint "easyedapro:HDR-TH_3P-P2.54-V-M")
      (libsource (lib "easyedapro") (part "HDR-M_2.54_1x3P"))
    )
    (comp (ref "LED1")
      (value "~")
      (footprint "easyedapro:LED_0603")
      (libsource (lib "easyedapro") (part "LED_R"))
    )
    (comp (ref "LED2")
      (value "~")
      (footprint "easyedapro:LED_0603")
      (libsource (lib "easyedapro") (part "LED_R"))
    )
    (comp (ref "LED3")
      (value "~")
      (footprint "easyedapro:LED_0603")
      (libsource (lib "easyedapro") (part "LED_R"))
    )
    (comp (ref "R1") (value "10K") (footprint "easyedapro:R0603") (libsource (lib "easyedapro") (part "电阻")))
    (comp (ref "R2") (value "1.2K") (footprint "easyedapro:R0603") (libsource (lib "easyedapro") (part "电阻")))
    (comp (ref "R3") (value "10K") (footprint "easyedapro:R0603") (libsource (lib "easyedapro") (part "电阻")))
    (comp (ref "R4") (value "1.2K") (footprint "easyedapro:R0603") (libsource (lib "easyedapro") (part "电阻")))
    (comp (ref "R5") (value "10K") (footprint "easyedapro:R0603") (libsource (lib "easyedapro") (part "电阻")))
    (comp (ref "R6") (value "1.2K") (footprint "easyedapro:R0603") (libsource (lib "easyedapro") (part "电阻")))
    (comp (ref "U2")
      (value "PC817C")
      (footprint "easyedapro:DIP-4_L4.6-W6.5-P2.54-LS7.6-BL")
      (fields (field (name "Manufacturer") "GOODWORK(固得沃克)"))
      (libsource (lib "easyedapro") (part "PC817-4"))
    )
    (comp (ref "U3")
      (value "1N4007 A7")
      (footprint "easyedapro:SMA_L4.3-W2.6-LS5.1-RD")
      (fields (field (name "Manufacturer") "TWGMC(台湾迪嘉)"))
      (libsource (lib "easyedapro") (part "1N4007_C9900004759"))
    )
    (comp (ref "U4")
      (value "KF128-3.81-2P")
      (footprint "easyedapro:CONN-TH_2P-P3.81_KF128-3.81-2P")
      (libsource (lib "easyedapro") (part "KF128-3.81-2P_C9900030554"))
    )
    (comp (ref "U5")
      (value "PC817C")
      (footprint "easyedapro:DIP-4_L4.6-W6.5-P2.54-LS7.6-BL")
      (fields (field (name "Manufacturer") "GOODWORK(固得沃克)"))
      (libsource (lib "easyedapro") (part "PC817-4"))
    )
    (comp (ref "U6")
      (value "1N4007 A7")
      (footprint "easyedapro:SMA_L4.3-W2.6-LS5.1-RD")
      (fields (field (name "Manufacturer") "TWGMC(台湾迪嘉)"))
      (libsource (lib "easyedapro") (part "1N4007_C9900004759"))
    )
    (comp (ref "U7")
      (value "KF128-3.81-2P")
      (footprint "easyedapro:CONN-TH_2P-P3.81_KF128-3.81-2P")
      (libsource (lib "easyedapro") (part "KF128-3.81-2P_C9900030554"))
    )
    (comp (ref "U8")
      (value "PC817C")
      (footprint "easyedapro:DIP-4_L4.6-W6.5-P2.54-LS7.6-BL")
      (fields (field (name "Manufacturer") "GOODWORK(固得沃克)"))
      (libsource (lib "easyedapro") (part "PC817-4"))
    )
    (comp (ref "U9")
      (value "1N4007 A7")
      (footprint "easyedapro:SMA_L4.3-W2.6-LS5.1-RD")
      (fields (field (name "Manufacturer") "TWGMC(台湾迪嘉)"))
      (libsource (lib "easyedapro") (part "1N4007_C9900004759"))
    )
    (comp (ref "U10")
      (value "KF128-3.81-2P")
      (footprint "easyedapro:CONN-TH_2P-P3.81_KF128-3.81-2P")
      (libsource (lib "easyedapro") (part "KF128-3.81-2P_C9900030554"))
    )
  )
  (nets
    (net (code "1") (name "3V3") (class "Default")
      (node (ref "C5") (pin "2") (pinfunction "2_2") (pintype "input"))
      (node (ref "LED4") (pin "2") (pinfunction "A_2") (pintype "input"))
      (node (ref "LED5") (pin "2") (pinfunction "A_2") (pintype "input"))
      (node (ref "LED6") (pin "2") (pinfunction "A_2") (pintype "input"))
      (node (ref "LED7") (pin "2") (pinfunction "A_2") (pintype "input"))
      (node (ref "LED8") (pin "2") (pinfunction "A_2") (pintype "input"))
      (node (ref "LED9") (pin "2") (pinfunction "A_2") (pintype "input"))
      (node (ref "R1") (pin "1") (pinfunction "1_1") (pintype "input"))
      (node (ref "R14") (pin "1") (pinfunction "1_1") (pintype "input"))
      (node (ref "R20") (pin "1") (pinfunction "1_1") (pintype "input"))
      (node (ref "R26") (pin "1") (pinfunction "1_1") (pintype "input"))
      (node (ref "R3") (pin "1") (pinfunction "1_1") (pintype "input"))
      (node (ref "R32") (pin "1") (pinfunction "1_1") (pintype "input"))
      (node (ref "R38") (pin "1") (pinfunction "1_1") (pintype "input"))
      (node (ref "R44") (pin "1") (pinfunction "1_1") (pintype "input"))
      (node (ref "R5") (pin "1") (pinfunction "1_1") (pintype "input"))
      (node (ref "U45") (pin "2") (pinfunction "VOUT_2") (pintype "unspecified"))
      (node (ref "U45") (pin "4") (pinfunction "VOUT_4") (pintype "unspecified"))
    )
    (net (code "2") (name "5V") (class "Default")
      (node (ref "C7") (pin "2") (pinfunction "2_2") (pintype "input"))
      (node (ref "U47") (pin "2") (pinfunction "VOUT_2") (pintype "unspecified"))
      (node (ref "U47") (pin "4") (pinfunction "VOUT_4") (pintype "unspecified"))
    )
    (net (code "3") (name "12V+") (class "Default")
      (node (ref "C4") (pin "1") (pinfunction "1_1") (pintype "input"))
      (node (ref "D10") (pin "1") (pinfunction "C_1") (pintype "unspecified"))
      (node (ref "D4") (pin "2") (pinfunction "A_2") (pintype "input"))
      (node (ref "D5") (pin "1") (pinfunction "C_1") (pintype "unspecified"))
      (node (ref "D6") (pin "1") (pinfunction "C_1") (pintype "unspecified"))
      (node (ref "D7") (pin "1") (pinfunction "C_1") (pintype "unspecified"))
      (node (ref "D8") (pin "1") (pinfunction "C_1") (pintype "unspecified"))
      (node (ref "D9") (pin "1") (pinfunction "C_1") (pintype "unspecified"))
      (node (ref "R12") (pin "2") (pinfunction "2_2") (pintype "input"))
      (node (ref "R13") (pin "2") (pinfunction "2_2") (pintype "input"))
      (node (ref "R18") (pin "2") (pinfunction "2_2") (pintype "input"))
      (node (ref "R19") (pin "2") (pinfunction "2_2") (pintype "input"))
      (node (ref "R24") (pin "2") (pinfunction "2_2") (pintype "input"))
      (node (ref "R25") (pin "2") (pinfunction "2_2") (pintype "input"))
      (node (ref "R30") (pin "2") (pinfunction "2_2") (pintype "input"))
      (node (ref "R31") (pin "2") (pinfunction "2_2") (pintype "input"))
      (node (ref "R36") (pin "2") (pinfunction "2_2") (pintype "input"))
      (node (ref "R37") (pin "2") (pinfunction "2_2") (pintype "input"))
      (node (ref "R42") (pin "2") (pinfunction "2_2") (pintype "input"))
      (node (ref "R43") (pin "2") (pinfunction "2_2") (pintype "input"))
      (node (ref "R54") (pin "1") (pinfunction "1_1") (pintype "input"))
      (node (ref "R55") (pin "1") (pinfunction "1_1") (pintype "input"))
      (node (ref "R57") (pin "1") (pinfunction "1_1") (pintype "input"))
      (node (ref "R58") (pin "1") (pinfunction "1_1") (pintype "input"))
      (node (ref "R59") (pin "1") (pinfunction "1_1") (pintype "input"))
      (node (ref "R60") (pin "1") (pinfunction "1_1") (pintype "input"))
      (node (ref "R7") (pin "2") (pinfunction "2_2") (pintype "input"))
      (node (ref "R8") (pin "2") (pinfunction "2_2") (pintype "input"))
      (node (ref "U12") (pin "2") (pinfunction "2_2") (pintype "unspecified"))
      (node (ref "U15") (pin "1") (pinfunction "1_1") (pintype "unspecified"))
      (node (ref "U19") (pin "1") (pinfunction "1_1") (pintype "unspecified"))
      (node (ref "U23") (pin "1") (pinfunction "1_1") (pintype "unspecified"))
      (node (ref "U27") (pin "1") (pinfunction "1_1") (pintype "unspecified"))
      (node (ref "U31") (pin "1") (pinfunction "1_1") (pintype "unspecified"))
      (node (ref "U35") (pin "1") (pinfunction "1_1") (pintype "unspecified"))
    )
    (net (code "4") (name "12V-") (class "Default")
      (node (ref "C4") (pin "2") (pinfunction "2_2") (pintype "input"))
      (node (ref "D4") (pin "1") (pinfunction "K_1") (pintype "input"))
      (node (ref "R17") (pin "1") (pinfunction "1_1") (pintype "input"))
      (node (ref "R23") (pin "1") (pinfunction "1_1") (pintype "input"))
      (node (ref "R29") (pin "1") (pinfunction "1_1") (pintype "input"))
      (node (ref "R35") (pin "1") (pinfunction "1_1") (pintype "input"))
      (node (ref "R41") (pin "1") (pinfunction "1_1") (pintype "input"))
      (node (ref "R47") (pin "1") (pinfunction "1_1") (pintype "input"))
      (node (ref "U11") (pin "2") (pinfunction "E_2") (pintype "input"))
      (node (ref "U12") (pin "1") (pinfunction "1_1") (pintype "unspecified"))
      (node (ref "U13") (pin "3") (pinfunction "EM_3") (pintype "unspecified"))
      (node (ref "U14") (pin "2") (pinfunction "E_2") (pintype "input"))
      (node (ref "U16") (pin "3") (pinfunction "EM_3") (pintype "unspecified"))
      (node (ref "U17") (pin "1") (pinfunction "S_1") (pintype "unspecified"))
      (node (ref "U17") (pin "2") (pinfunction "S_2") (pintype "unspecified"))
      (node (ref "U17") (pin "3") (pinfunction "S_3") (pintype "unspecified"))
      (node (ref "U18") (pin "2") (pinfunction "E_2") (pintype "input"))
      (node (ref "U20") (pin "3") (pinfunction "EM_3") (pintype "unspecified"))
      (node (ref "U21") (pin "1") (pinfunction "S_1") (pintype "unspecified"))
      (node (ref "U21") (pin "2") (pinfunction "S_2") (pintype "unspecified"))
      (node (ref "U21") (pin "3") (pinfunction "S_3") (pintype "unspecified"))
      (node (ref "U22") (pin "2") (pinfunction "E_2") (pintype "input"))
      (node (ref "U24") (pin "3") (pinfunction "EM_3") (pintype "unspecified"))
      (node (ref "U25") (pin "1") (pinfunction "S_1") (pintype "unspecified"))
      (node (ref "U25") (pin "2") (pinfunction "S_2") (pintype "unspecified"))
      (node (ref "U25") (pin "3") (pinfunction "S_3") (pintype "unspecified"))
      (node (ref "U26") (pin "2") (pinfunction "E_2") (pintype "input"))
      (node (ref "U28") (pin "3") (pinfunction "EM_3") (pintype "unspecified"))
      (node (ref "U29") (pin "1") (pinfunction "S_1") (pintype "unspecified"))
      (node (ref "U29") (pin "2") (pinfunction "S_2") (pintype "unspecified"))
      (node (ref "U29") (pin "3") (pinfunction "S_3") (pintype "unspecified"))
      (node (ref "U30") (pin "2") (pinfunction "E_2") (pintype "input"))
      (node (ref "U32") (pin "3") (pinfunction "EM_3") (pintype "unspecified"))
      (node (ref "U33") (pin "1") (pinfunction "S_1") (pintype "unspecified"))
      (node (ref "U33") (pin "2") (pinfunction "S_2") (pintype "unspecified"))
      (node (ref "U33") (pin "3") (pinfunction "S_3") (pintype "unspecified"))
      (node (ref "U34") (pin "2") (pinfunction "E_2") (pintype "input"))
      (node (ref "U36") (pin "3") (pinfunction "EM_3") (pintype "unspecified"))
      (node (ref "U37") (pin "1") (pinfunction "S_1") (pintype "unspecified"))
      (node (ref "U37") (pin "2") (pinfunction "S_2") (pintype "unspecified"))
      (node (ref "U37") (pin "3") (pinfunction "S_3") (pintype "unspecified"))
      (node (ref "U38") (pin "2") (pinfunction "E_2") (pintype "input"))
      (node (ref "ZD1") (pin "1") (pinfunction "A_1") (pintype "unspecified"))
      (node (ref "ZD2") (pin "1") (pinfunction "A_1") (pintype "unspecified"))
      (node (ref "ZD3") (pin "1") (pinfunction "A_1") (pintype "unspecified"))
      (node (ref "ZD4") (pin "1") (pinfunction "A_1") (pintype "unspecified"))
      (node (ref "ZD5") (pin "1") (pinfunction "A_1") (pintype "unspecified"))
      (node (ref "ZD6") (pin "1") (pinfunction "A_1") (pintype "unspecified"))
    )
    (net (code "5") (name "EN") (class "Default")
      (node (ref "H10") (pin "2") (pinfunction "2_2") (pintype "unspecified"))
      (node (ref "H3") (pin "2") (pinfunction "2_2") (pintype "unspecified"))
      (node (ref "R10") (pin "1") (pinfunction "1_1") (pintype "input"))
    )
    (net (code "6") (name "EN_OUT") (class "Default")
      (node (ref "U14") (pin "3") (pinfunction "C_3") (pintype "input"))
    )
    (net (code "7") (name "GATE1") (class "Default")
      (node (ref "R15") (pin "2") (pinfunction "2_2") (pintype "input"))
      (node (ref "R17") (pin "2") (pinfunction "2_2") (pintype "input"))
      (node (ref "U17") (pin "4") (pinfunction "G_4") (pintype "unspecified"))
      (node (ref "ZD1") (pin "2") (pinfunction "K_2") (pintype "unspecified"))
    )
    (net (code "8") (name "GATE2") (class "Default")
      (node (ref "R21") (pin "2") (pinfunction "2_2") (pintype "input"))
      (node (ref "R23") (pin "2") (pinfunction "2_2") (pintype "input"))
      (node (ref "U21") (pin "4") (pinfunction "G_4") (pintype "unspecified"))
      (node (ref "ZD2") (pin "2") (pinfunction "K_2") (pintype "unspecified"))
    )
    (net (code "9") (name "GATE3") (class "Default")
      (node (ref "R27") (pin "2") (pinfunction "2_2") (pintype "input"))
      (node (ref "R29") (pin "2") (pinfunction "2_2") (pintype "input"))
      (node (ref "U25") (pin "4") (pinfunction "G_4") (pintype "unspecified"))
      (node (ref "ZD3") (pin "2") (pinfunction "K_2") (pintype "unspecified"))
    )
    (net (code "10") (name "GATE4") (class "Default")
      (node (ref "R33") (pin "2") (pinfunction "2_2") (pintype "input"))
      (node (ref "R35") (pin "2") (pinfunction "2_2") (pintype "input"))
      (node (ref "U29") (pin "4") (pinfunction "G_4") (pintype "unspecified"))
      (node (ref "ZD4") (pin "2") (pinfunction "K_2") (pintype "unspecified"))
    )
    (net (code "11") (name "GATE5") (class "Default")
      (node (ref "R39") (pin "2") (pinfunction "2_2") (pintype "input"))
      (node (ref "R41") (pin "2") (pinfunction "2_2") (pintype "input"))
      (node (ref "U33") (pin "4") (pinfunction "G_4") (pintype "unspecified"))
      (node (ref "ZD5") (pin "2") (pinfunction "K_2") (pintype "unspecified"))
    )
    (net (code "12") (name "GATE6") (class "Default")
      (node (ref "R45") (pin "2") (pinfunction "2_2") (pintype "input"))
      (node (ref "R47") (pin "2") (pinfunction "2_2") (pintype "input"))
      (node (ref "U37") (pin "4") (pinfunction "G_4") (pintype "unspecified"))
      (node (ref "ZD6") (pin "2") (pinfunction "K_2") (pintype "unspecified"))
    )
    (net (code "13") (name "GND") (class "Default")
      (node (ref "C5") (pin "1") (pinfunction "1_1") (pintype "input"))
      (node (ref "C6") (pin "1") (pinfunction "1_1") (pintype "input"))
      (node (ref "C7") (pin "1") (pinfunction "1_1") (pintype "input"))
      (node (ref "C8") (pin "1") (pinfunction "1_1") (pintype "input"))
      (node (ref "H10") (pin "1") (pinfunction "1_1") (pintype "unspecified"))
      (node (ref "H3") (pin "1") (pinfunction "1_1") (pintype "unspecified"))
      (node (ref "U1") (pin "2") (pinfunction "2_2") (pintype "unspecified"))
      (node (ref "U13") (pin "2") (pinfunction "C_2") (pintype "unspecified"))
      (node (ref "U2") (pin "3") (pinfunction "EM_3") (pintype "unspecified"))
      (node (ref "U39") (pin "2") (pinfunction "E_2") (pintype "input"))
      (node (ref "U40") (pin "2") (pinfunction "E_2") (pintype "input"))
      (node (ref "U41") (pin "2") (pinfunction "E_2") (pintype "input"))
      (node (ref "U42") (pin "2") (pinfunction "E_2") (pintype "input"))
      (node (ref "U43") (pin "2") (pinfunction "E_2") (pintype "input"))
      (node (ref "U44") (pin "2") (pinfunction "E_2") (pintype "input"))
      (node (ref "U45") (pin "1") (pinfunction "GND_1") (pintype "unspecified"))
      (node (ref "U47") (pin "1") (pinfunction "GND_1") (pintype "unspecified"))
      (node (ref "U5") (pin "3") (pinfunction "EM_3") (pintype "unspecified"))
      (node (ref "U8") (pin "3") (pinfunction "EM_3") (pintype "unspecified"))
    )
    (net (code "14") (name "L1-OUT-") (class "Default")
      (node (ref "D5") (pin "2") (pinfunction "A_2") (pintype "unspecified"))
      (node (ref "LED10") (pin "1") (pinfunction "C_1") (pintype "input"))
      (node (ref "U15") (pin "2") (pinfunction "2_2") (pintype "unspecified"))
      (node (ref "U17") (pin "5") (pinfunction "D_5") (pintype "unspecified"))
      (node (ref "U17") (pin "6") (pinfunction "D_6") (pintype "unspecified"))
      (node (ref "U17") (pin "7") (pinfunction "D_7") (pintype "unspecified"))
      (node (ref "U17") (pin "8") (pinfunction "D_8") (pintype "unspecified"))
    )
    (net (code "15") (name "L1-VIN+") (class "Default")
      (node (ref "D1") (pin "2") (pinfunction "2_2") (pintype "unspecified"))
      (node (ref "U3") (pin "2") (pinfunction "A_2") (pintype "unspecified"))
      (node (ref "U4") (pin "1") (pinfunction "1_1") (pintype "unspecified"))
    )
    (net (code "16") (name "L1-VIN-") (class "Default")
      (node (ref "C1") (pin "1") (pinfunction "1_1") (pintype "input"))
      (node (ref "D1") (pin "1") (pinfunction "1_1") (pintype "unspecified"))
      (node (ref "U2") (pin "2") (pinfunction "C_2") (pintype "unspecified"))
      (node (ref "U4") (pin "2") (pinfunction "2_2") (pintype "unspecified"))
    )
    (net (code "17") (name "L2-OUT-") (class "Default")
      (node (ref "D6") (pin "2") (pinfunction "A_2") (pintype "unspecified"))
      (node (ref "LED11") (pin "1") (pinfunction "C_1") (pintype "input"))
      (node (ref "U19") (pin "2") (pinfunction "2_2") (pintype "unspecified"))
      (node (ref "U21") (pin "5") (pinfunction "D_5") (pintype "unspecified"))
      (node (ref "U21") (pin "6") (pinfunction "D_6") (pintype "unspecified"))
      (node (ref "U21") (pin "7") (pinfunction "D_7") (pintype "unspecified"))
      (node (ref "U21") (pin "8") (pinfunction "D_8") (pintype "unspecified"))
    )
    (net (code "18") (name "L2-VIN+") (class "Default")
      (node (ref "D2") (pin "2") (pinfunction "2_2") (pintype "unspecified"))
      (node (ref "U6") (pin "2") (pinfunction "A_2") (pintype "unspecified"))
      (node (ref "U7") (pin "1") (pinfunction "1_1") (pintype "unspecified"))
    )
    (net (code "19") (name "L2-VIN-") (class "Default")
      (node (ref "C2") (pin "1") (pinfunction "1_1") (pintype "input"))
      (node (ref "D2") (pin "1") (pinfunction "1_1") (pintype "unspecified"))
      (node (ref "U5") (pin "2") (pinfunction "C_2") (pintype "unspecified"))
      (node (ref "U7") (pin "2") (pinfunction "2_2") (pintype "unspecified"))
    )
    (net (code "20") (name "L3-OUT-") (class "Default")
      (node (ref "D7") (pin "2") (pinfunction "A_2") (pintype "unspecified"))
      (node (ref "LED13") (pin "1") (pinfunction "C_1") (pintype "input"))
      (node (ref "U23") (pin "2") (pinfunction "2_2") (pintype "unspecified"))
      (node (ref "U25") (pin "5") (pinfunction "D_5") (pintype "unspecified"))
      (node (ref "U25") (pin "6") (pinfunction "D_6") (pintype "unspecified"))
      (node (ref "U25") (pin "7") (pinfunction "D_7") (pintype "unspecified"))
      (node (ref "U25") (pin "8") (pinfunction "D_8") (pintype "unspecified"))
    )
    (net (code "21") (name "L3-VIN+") (class "Default")
      (node (ref "D3") (pin "2") (pinfunction "2_2") (pintype "unspecified"))
      (node (ref "U10") (pin "1") (pinfunction "1_1") (pintype "unspecified"))
      (node (ref "U9") (pin "2") (pinfunction "A_2") (pintype "unspecified"))
    )
    (net (code "22") (name "L3-VIN-") (class "Default")
      (node (ref "C3") (pin "1") (pinfunction "1_1") (pintype "input"))
      (node (ref "D3") (pin "1") (pinfunction "1_1") (pintype "unspecified"))
      (node (ref "U10") (pin "2") (pinfunction "2_2") (pintype "unspecified"))
      (node (ref "U8") (pin "2") (pinfunction "C_2") (pintype "unspecified"))
    )
    (net (code "23") (name "L4-OUT-") (class "Default")
      (node (ref "D8") (pin "2") (pinfunction "A_2") (pintype "unspecified"))
      (node (ref "LED14") (pin "1") (pinfunction "C_1") (pintype "input"))
      (node (ref "U27") (pin "2") (pinfunction "2_2") (pintype "unspecified"))
      (node (ref "U29") (pin "5") (pinfunction "D_5") (pintype "unspecified"))
      (node (ref "U29") (pin "6") (pinfunction "D_6") (pintype "unspecified"))
      (node (ref "U29") (pin "7") (pinfunction "D_7") (pintype "unspecified"))
      (node (ref "U29") (pin "8") (pinfunction "D_8") (pintype "unspecified"))
    )
    (net (code "24") (name "L5-OUT-") (class "Default")
      (node (ref "D9") (pin "2") (pinfunction "A_2") (pintype "unspecified"))
      (node (ref "LED15") (pin "1") (pinfunction "C_1") (pintype "input"))
      (node (ref "U31") (pin "2") (pinfunction "2_2") (pintype "unspecified"))
      (node (ref "U33") (pin "5") (pinfunction "D_5") (pintype "unspecified"))
      (node (ref "U33") (pin "6") (pinfunction "D_6") (pintype "unspecified"))
      (node (ref "U33") (pin "7") (pinfunction "D_7") (pintype "unspecified"))
      (node (ref "U33") (pin "8") (pinfunction "D_8") (pintype "unspecified"))
    )
    (net (code "25") (name "L6-OUT-") (class "Default")
      (node (ref "D10") (pin "2") (pinfunction "A_2") (pintype "unspecified"))
      (node (ref "LED16") (pin "1") (pinfunction "C_1") (pintype "input"))
      (node (ref "U35") (pin "2") (pinfunction "2_2") (pintype "unspecified"))
      (node (ref "U37") (pin "5") (pinfunction "D_5") (pintype "unspecified"))
      (node (ref "U37") (pin "6") (pinfunction "D_6") (pintype "unspecified"))
      (node (ref "U37") (pin "7") (pinfunction "D_7") (pintype "unspecified"))
      (node (ref "U37") (pin "8") (pinfunction "D_8") (pintype "unspecified"))
    )
    (net (code "26") (name "LINE_1") (class "Default")
      (node (ref "H10") (pin "3") (pinfunction "3_3") (pintype "unspecified"))
      (node (ref "H3") (pin "3") (pinfunction "3_3") (pintype "unspecified"))
      (node (ref "R62") (pin "1") (pinfunction "1_1") (pintype "input"))
    )
    (net (code "27") (name "LINE_2") (class "Default")
      (node (ref "H10") (pin "4") (pinfunction "4_4") (pintype "unspecified"))
      (node (ref "H3") (pin "4") (pinfunction "4_4") (pintype "unspecified"))
      (node (ref "R63") (pin "1") (pinfunction "1_1") (pintype "input"))
    )
    (net (code "28") (name "LINE_3") (class "Default")
      (node (ref "H10") (pin "5") (pinfunction "5_5") (pintype "unspecified"))
      (node (ref "H3") (pin "5") (pinfunction "5_5") (pintype "unspecified"))
      (node (ref "R64") (pin "1") (pinfunction "1_1") (pintype "input"))
    )
    (net (code "29") (name "LINE_4") (class "Default")
      (node (ref "H10") (pin "6") (pinfunction "6_6") (pintype "unspecified"))
      (node (ref "H3") (pin "6") (pinfunction "6_6") (pintype "unspecified"))
      (node (ref "R65") (pin "1") (pinfunction "1_1") (pintype "input"))
    )
    (net (code "30") (name "LINE_5") (class "Default")
      (node (ref "H10") (pin "7") (pinfunction "7_7") (pintype "unspecified"))
      (node (ref "H3") (pin "7") (pinfunction "7_7") (pintype "unspecified"))
      (node (ref "R66") (pin "1") (pinfunction "1_1") (pintype "input"))
    )
    (net (code "31") (name "LINE_6") (class "Default")
      (node (ref "H10") (pin "8") (pinfunction "8_8") (pintype "unspecified"))
      (node (ref "H3") (pin "8") (pinfunction "8_8") (pintype "unspecified"))
      (node (ref "R67") (pin "1") (pinfunction "1_1") (pintype "input"))
    )
    (net (code "32") (name "LINE_PC817_2_1") (class "Default")
      (node (ref "R53") (pin "2") (pinfunction "2_2") (pintype "input"))
      (node (ref "U16") (pin "2") (pinfunction "C_2") (pintype "unspecified"))
      (node (ref "U39") (pin "3") (pinfunction "C_3") (pintype "input"))
    )
    (net (code "33") (name "LINE_PC817_2_2") (class "Default")
      (node (ref "R52") (pin "2") (pinfunction "2_2") (pintype "input"))
      (node (ref "U20") (pin "2") (pinfunction "C_2") (pintype "unspecified"))
      (node (ref "U40") (pin "3") (pinfunction "C_3") (pintype "input"))
    )
    (net (code "34") (name "LINE_PC817_2_3") (class "Default")
      (node (ref "R51") (pin "2") (pinfunction "2_2") (pintype "input"))
      (node (ref "U24") (pin "2") (pinfunction "C_2") (pintype "unspecified"))
      (node (ref "U41") (pin "3") (pinfunction "C_3") (pintype "input"))
    )
    (net (code "35") (name "LINE_PC817_2_4") (class "Default")
      (node (ref "R50") (pin "2") (pinfunction "2_2") (pintype "input"))
      (node (ref "U28") (pin "2") (pinfunction "C_2") (pintype "unspecified"))
      (node (ref "U42") (pin "3") (pinfunction "C_3") (pintype "input"))
    )
    (net (code "36") (name "LINE_PC817_2_5") (class "Default")
      (node (ref "R49") (pin "2") (pinfunction "2_2") (pintype "input"))
      (node (ref "U32") (pin "2") (pinfunction "C_2") (pintype "unspecified"))
      (node (ref "U43") (pin "3") (pinfunction "C_3") (pintype "input"))
    )
    (net (code "37") (name "LINE_PC817_2_6") (class "Default")
      (node (ref "R48") (pin "2") (pinfunction "2_2") (pintype "input"))
      (node (ref "U36") (pin "2") (pinfunction "C_2") (pintype "unspecified"))
      (node (ref "U44") (pin "3") (pinfunction "C_3") (pintype "input"))
    )
    (net (code "38") (name "Net-(H2-Pad2)") (class "Default")
      (node (ref "H2") (pin "2") (pinfunction "2_2") (pintype "input"))
      (node (ref "R11") (pin "2") (pinfunction "2_2") (pintype "input"))
    )
    (net (code "39") (name "Net-(H4-Pad2)") (class "Default")
      (node (ref "H4") (pin "2") (pinfunction "2_2") (pintype "input"))
      (node (ref "R15") (pin "1") (pinfunction "1_1") (pintype "input"))
    )
    (net (code "40") (name "Net-(H5-Pad2)") (class "Default")
      (node (ref "H5") (pin "2") (pinfunction "2_2") (pintype "input"))
      (node (ref "R21") (pin "1") (pinfunction "1_1") (pintype "input"))
    )
    (net (code "41") (name "Net-(H6-Pad2)") (class "Default")
      (node (ref "H6") (pin "2") (pinfunction "2_2") (pintype "input"))
      (node (ref "R27") (pin "1") (pinfunction "1_1") (pintype "input"))
    )
    (net (code "42") (name "Net-(H7-Pad2)") (class "Default")
      (node (ref "H7") (pin "2") (pinfunction "2_2") (pintype "input"))
      (node (ref "R33") (pin "1") (pinfunction "1_1") (pintype "input"))
    )
    (net (code "43") (name "Net-(H8-Pad2)") (class "Default")
      (node (ref "H8") (pin "2") (pinfunction "2_2") (pintype "input"))
      (node (ref "R39") (pin "1") (pinfunction "1_1") (pintype "input"))
    )
    (net (code "44") (name "Net-(H9-Pad2)") (class "Default")
      (node (ref "H9") (pin "2") (pinfunction "2_2") (pintype "input"))
      (node (ref "R45") (pin "1") (pinfunction "1_1") (pintype "input"))
    )
    (net (code "45") (name "Net-(LED1-A)") (class "Default")
      (node (ref "LED1") (pin "2") (pinfunction "A_2") (pintype "input"))
      (node (ref "R2") (pin "1") (pinfunction "1_1") (pintype "input"))
    )
    (net (code "46") (name "Net-(LED1-C)") (class "Default")
      (node (ref "LED1") (pin "1") (pinfunction "C_1") (pintype "input"))
      (node (ref "U2") (pin "1") (pinfunction "A_1") (pintype "unspecified"))
    )
    (net (code "47") (name "Net-(LED2-A)") (class "Default")
      (node (ref "LED2") (pin "2") (pinfunction "A_2") (pintype "input"))
      (node (ref "R4") (pin "1") (pinfunction "1_1") (pintype "input"))
    )
    (net (code "48") (name "Net-(LED2-C)") (class "Default")
      (node (ref "LED2") (pin "1") (pinfunction "C_1") (pintype "input"))
      (node (ref "U5") (pin "1") (pinfunction "A_1") (pintype "unspecified"))
    )
    (net (code "49") (name "Net-(LED3-A)") (class "Default")
      (node (ref "LED3") (pin "2") (pinfunction "A_2") (pintype "input"))
      (node (ref "R6") (pin "1") (pinfunction "1_1") (pintype "input"))
    )
    (net (code "50") (name "Net-(LED3-C)") (class "Default")
      (node (ref "LED3") (pin "1") (pinfunction "C_1") (pintype "input"))
      (node (ref "U8") (pin "1") (pinfunction "A_1") (pintype "unspecified"))
    )
    (net (code "51") (name "Net-(LED4-C)") (class "Default")
      (node (ref "LED4") (pin "1") (pinfunction "C_1") (pintype "input"))
      (node (ref "R48") (pin "1") (pinfunction "1_1") (pintype "input"))
    )
    (net (code "52") (name "Net-(LED5-C)") (class "Default")
      (node (ref "LED5") (pin "1") (pinfunction "C_1") (pintype "input"))
      (node (ref "R49") (pin "1") (pinfunction "1_1") (pintype "input"))
    )
    (net (code "53") (name "Net-(LED6-C)") (class "Default")
      (node (ref "LED6") (pin "1") (pinfunction "C_1") (pintype "input"))
      (node (ref "R50") (pin "1") (pinfunction "1_1") (pintype "input"))
    )
    (net (code "54") (name "Net-(LED7-C)") (class "Default")
      (node (ref "LED7") (pin "1") (pinfunction "C_1") (pintype "input"))
      (node (ref "R51") (pin "1") (pinfunction "1_1") (pintype "input"))
    )
    (net (code "55") (name "Net-(LED8-C)") (class "Default")
      (node (ref "LED8") (pin "1") (pinfunction "C_1") (pintype "input"))
      (node (ref "R52") (pin "1") (pinfunction "1_1") (pintype "input"))
    )
    (net (code "56") (name "Net-(LED9-C)") (class "Default")
      (node (ref "LED9") (pin "1") (pinfunction "C_1") (pintype "input"))
      (node (ref "R53") (pin "1") (pinfunction "1_1") (pintype "input"))
    )
    (net (code "57") (name "Net-(LED10-A)") (class "Default")
      (node (ref "LED10") (pin "2") (pinfunction "A_2") (pintype "input"))
      (node (ref "R54") (pin "2") (pinfunction "2_2") (pintype "input"))
    )
    (net (code "58") (name "Net-(LED11-A)") (class "Default")
      (node (ref "LED11") (pin "2") (pinfunction "A_2") (pintype "input"))
      (node (ref "R55") (pin "2") (pinfunction "2_2") (pintype "input"))
    )
    (net (code "59") (name "Net-(LED13-A)") (class "Default")
      (node (ref "LED13") (pin "2") (pinfunction "A_2") (pintype "input"))
      (node (ref "R57") (pin "2") (pinfunction "2_2") (pintype "input"))
    )
    (net (code "60") (name "Net-(LED14-A)") (class "Default")
      (node (ref "LED14") (pin "2") (pinfunction "A_2") (pintype "input"))
      (node (ref "R58") (pin "2") (pinfunction "2_2") (pintype "input"))
    )
    (net (code "61") (name "Net-(LED15-A)") (class "Default")
      (node (ref "LED15") (pin "2") (pinfunction "A_2") (pintype "input"))
      (node (ref "R59") (pin "2") (pinfunction "2_2") (pintype "input"))
    )
    (net (code "62") (name "Net-(LED16-A)") (class "Default")
      (node (ref "LED16") (pin "2") (pinfunction "A_2") (pintype "input"))
      (node (ref "R60") (pin "2") (pinfunction "2_2") (pintype "input"))
    )
    (net (code "63") (name "Net-(U2-COL)") (class "Default")
      (node (ref "H1") (pin "3") (pinfunction "3_3") (pintype "input"))
      (node (ref "R1") (pin "2") (pinfunction "2_2") (pintype "input"))
      (node (ref "U2") (pin "4") (pinfunction "COL_4") (pintype "unspecified"))
    )
    (net (code "64") (name "Net-(U3-K)") (class "Default")
      (node (ref "C1") (pin "2") (pinfunction "2_2") (pintype "input"))
      (node (ref "R2") (pin "2") (pinfunction "2_2") (pintype "input"))
      (node (ref "U3") (pin "1") (pinfunction "K_1") (pintype "unspecified"))
    )
    (net (code "65") (name "Net-(U5-COL)") (class "Default")
      (node (ref "H1") (pin "2") (pinfunction "2_2") (pintype "input"))
      (node (ref "R3") (pin "2") (pinfunction "2_2") (pintype "input"))
      (node (ref "U5") (pin "4") (pinfunction "COL_4") (pintype "unspecified"))
    )
    (net (code "66") (name "Net-(U6-K)") (class "Default")
      (node (ref "C2") (pin "2") (pinfunction "2_2") (pintype "input"))
      (node (ref "R4") (pin "2") (pinfunction "2_2") (pintype "input"))
      (node (ref "U6") (pin "1") (pinfunction "K_1") (pintype "unspecified"))
    )
    (net (code "67") (name "Net-(U8-COL)") (class "Default")
      (node (ref "H1") (pin "1") (pinfunction "1_1") (pintype "input"))
      (node (ref "R5") (pin "2") (pinfunction "2_2") (pintype "input"))
      (node (ref "U8") (pin "4") (pinfunction "COL_4") (pintype "unspecified"))
    )
    (net (code "68") (name "Net-(U9-K)") (class "Default")
      (node (ref "C3") (pin "2") (pinfunction "2_2") (pintype "input"))
      (node (ref "R6") (pin "2") (pinfunction "2_2") (pintype "input"))
      (node (ref "U9") (pin "1") (pinfunction "K_1") (pintype "unspecified"))
    )
    (net (code "69") (name "Net-(U11-B)") (class "Default")
      (node (ref "R9") (pin "2") (pinfunction "2_2") (pintype "input"))
      (node (ref "U11") (pin "1") (pinfunction "B_1") (pintype "input"))
    )
    (net (code "70") (name "Net-(U11-C)") (class "Default")
      (node (ref "H2") (pin "1") (pinfunction "1_1") (pintype "input"))
      (node (ref "R7") (pin "1") (pinfunction "1_1") (pintype "input"))
      (node (ref "U11") (pin "3") (pinfunction "C_3") (pintype "input"))
    )
    (net (code "71") (name "Net-(U13-A)") (class "Default")
      (node (ref "R10") (pin "2") (pinfunction "2_2") (pintype "input"))
      (node (ref "U13") (pin "1") (pinfunction "A_1") (pintype "unspecified"))
    )
    (net (code "72") (name "Net-(U13-COL)") (class "Default")
      (node (ref "H2") (pin "3") (pinfunction "3_3") (pintype "input"))
      (node (ref "R8") (pin "1") (pinfunction "1_1") (pintype "input"))
      (node (ref "R9") (pin "1") (pinfunction "1_1") (pintype "input"))
      (node (ref "U13") (pin "4") (pinfunction "COL_4") (pintype "unspecified"))
    )
    (net (code "73") (name "Net-(U14-B)") (class "Default")
      (node (ref "R11") (pin "1") (pinfunction "1_1") (pintype "input"))
      (node (ref "U14") (pin "1") (pinfunction "B_1") (pintype "input"))
    )
    (net (code "74") (name "Net-(U16-A)") (class "Default")
      (node (ref "R14") (pin "2") (pinfunction "2_2") (pintype "input"))
      (node (ref "U16") (pin "1") (pinfunction "A_1") (pintype "unspecified"))
    )
    (net (code "75") (name "Net-(U16-COL)") (class "Default")
      (node (ref "H4") (pin "3") (pinfunction "3_3") (pintype "input"))
      (node (ref "R12") (pin "1") (pinfunction "1_1") (pintype "input"))
      (node (ref "R16") (pin "2") (pinfunction "2_2") (pintype "input"))
      (node (ref "U16") (pin "4") (pinfunction "COL_4") (pintype "unspecified"))
    )
    (net (code "76") (name "Net-(U18-B)") (class "Default")
      (node (ref "R16") (pin "1") (pinfunction "1_1") (pintype "input"))
      (node (ref "U18") (pin "1") (pinfunction "B_1") (pintype "input"))
    )
    (net (code "77") (name "Net-(U18-C)") (class "Default")
      (node (ref "H4") (pin "1") (pinfunction "1_1") (pintype "input"))
      (node (ref "R13") (pin "1") (pinfunction "1_1") (pintype "input"))
      (node (ref "U18") (pin "3") (pinfunction "C_3") (pintype "input"))
    )
    (net (code "78") (name "Net-(U20-A)") (class "Default")
      (node (ref "R20") (pin "2") (pinfunction "2_2") (pintype "input"))
      (node (ref "U20") (pin "1") (pinfunction "A_1") (pintype "unspecified"))
    )
    (net (code "79") (name "Net-(U20-COL)") (class "Default")
      (node (ref "H5") (pin "3") (pinfunction "3_3") (pintype "input"))
      (node (ref "R18") (pin "1") (pinfunction "1_1") (pintype "input"))
      (node (ref "R22") (pin "2") (pinfunction "2_2") (pintype "input"))
      (node (ref "U20") (pin "4") (pinfunction "COL_4") (pintype "unspecified"))
    )
    (net (code "80") (name "Net-(U22-B)") (class "Default")
      (node (ref "R22") (pin "1") (pinfunction "1_1") (pintype "input"))
      (node (ref "U22") (pin "1") (pinfunction "B_1") (pintype "input"))
    )
    (net (code "81") (name "Net-(U22-C)") (class "Default")
      (node (ref "H5") (pin "1") (pinfunction "1_1") (pintype "input"))
      (node (ref "R19") (pin "1") (pinfunction "1_1") (pintype "input"))
      (node (ref "U22") (pin "3") (pinfunction "C_3") (pintype "input"))
    )
    (net (code "82") (name "Net-(U24-A)") (class "Default")
      (node (ref "R26") (pin "2") (pinfunction "2_2") (pintype "input"))
      (node (ref "U24") (pin "1") (pinfunction "A_1") (pintype "unspecified"))
    )
    (net (code "83") (name "Net-(U24-COL)") (class "Default")
      (node (ref "H6") (pin "3") (pinfunction "3_3") (pintype "input"))
      (node (ref "R24") (pin "1") (pinfunction "1_1") (pintype "input"))
      (node (ref "R28") (pin "2") (pinfunction "2_2") (pintype "input"))
      (node (ref "U24") (pin "4") (pinfunction "COL_4") (pintype "unspecified"))
    )
    (net (code "84") (name "Net-(U26-B)") (class "Default")
      (node (ref "R28") (pin "1") (pinfunction "1_1") (pintype "input"))
      (node (ref "U26") (pin "1") (pinfunction "B_1") (pintype "input"))
    )
    (net (code "85") (name "Net-(U26-C)") (class "Default")
      (node (ref "H6") (pin "1") (pinfunction "1_1") (pintype "input"))
      (node (ref "R25") (pin "1") (pinfunction "1_1") (pintype "input"))
      (node (ref "U26") (pin "3") (pinfunction "C_3") (pintype "input"))
    )
    (net (code "86") (name "Net-(U28-A)") (class "Default")
      (node (ref "R32") (pin "2") (pinfunction "2_2") (pintype "input"))
      (node (ref "U28") (pin "1") (pinfunction "A_1") (pintype "unspecified"))
    )
    (net (code "87") (name "Net-(U28-COL)") (class "Default")
      (node (ref "H7") (pin "3") (pinfunction "3_3") (pintype "input"))
      (node (ref "R30") (pin "1") (pinfunction "1_1") (pintype "input"))
      (node (ref "R34") (pin "2") (pinfunction "2_2") (pintype "input"))
      (node (ref "U28") (pin "4") (pinfunction "COL_4") (pintype "unspecified"))
    )
    (net (code "88") (name "Net-(U30-B)") (class "Default")
      (node (ref "R34") (pin "1") (pinfunction "1_1") (pintype "input"))
      (node (ref "U30") (pin "1") (pinfunction "B_1") (pintype "input"))
    )
    (net (code "89") (name "Net-(U30-C)") (class "Default")
      (node (ref "H7") (pin "1") (pinfunction "1_1") (pintype "input"))
      (node (ref "R31") (pin "1") (pinfunction "1_1") (pintype "input"))
      (node (ref "U30") (pin "3") (pinfunction "C_3") (pintype "input"))
    )
    (net (code "90") (name "Net-(U32-A)") (class "Default")
      (node (ref "R38") (pin "2") (pinfunction "2_2") (pintype "input"))
      (node (ref "U32") (pin "1") (pinfunction "A_1") (pintype "unspecified"))
    )
    (net (code "91") (name "Net-(U32-COL)") (class "Default")
      (node (ref "H8") (pin "3") (pinfunction "3_3") (pintype "input"))
      (node (ref "R36") (pin "1") (pinfunction "1_1") (pintype "input"))
      (node (ref "R40") (pin "2") (pinfunction "2_2") (pintype "input"))
      (node (ref "U32") (pin "4") (pinfunction "COL_4") (pintype "unspecified"))
    )
    (net (code "92") (name "Net-(U34-B)") (class "Default")
      (node (ref "R40") (pin "1") (pinfunction "1_1") (pintype "input"))
      (node (ref "U34") (pin "1") (pinfunction "B_1") (pintype "input"))
    )
    (net (code "93") (name "Net-(U34-C)") (class "Default")
      (node (ref "H8") (pin "1") (pinfunction "1_1") (pintype "input"))
      (node (ref "R37") (pin "1") (pinfunction "1_1") (pintype "input"))
      (node (ref "U34") (pin "3") (pinfunction "C_3") (pintype "input"))
    )
    (net (code "94") (name "Net-(U36-A)") (class "Default")
      (node (ref "R44") (pin "2") (pinfunction "2_2") (pintype "input"))
      (node (ref "U36") (pin "1") (pinfunction "A_1") (pintype "unspecified"))
    )
    (net (code "95") (name "Net-(U36-COL)") (class "Default")
      (node (ref "H9") (pin "3") (pinfunction "3_3") (pintype "input"))
      (node (ref "R42") (pin "1") (pinfunction "1_1") (pintype "input"))
      (node (ref "R46") (pin "2") (pinfunction "2_2") (pintype "input"))
      (node (ref "U36") (pin "4") (pinfunction "COL_4") (pintype "unspecified"))
    )
    (net (code "96") (name "Net-(U38-B)") (class "Default")
      (node (ref "R46") (pin "1") (pinfunction "1_1") (pintype "input"))
      (node (ref "U38") (pin "1") (pinfunction "B_1") (pintype "input"))
    )
    (net (code "97") (name "Net-(U38-C)") (class "Default")
      (node (ref "H9") (pin "1") (pinfunction "1_1") (pintype "input"))
      (node (ref "R43") (pin "1") (pinfunction "1_1") (pintype "input"))
      (node (ref "U38") (pin "3") (pinfunction "C_3") (pintype "input"))
    )
    (net (code "98") (name "Net-(U39-B)") (class "Default")
      (node (ref "R62") (pin "2") (pinfunction "2_2") (pintype "input"))
      (node (ref "U39") (pin "1") (pinfunction "B_1") (pintype "input"))
    )
    (net (code "99") (name "Net-(U40-B)") (class "Default")
      (node (ref "R63") (pin "2") (pinfunction "2_2") (pintype "input"))
      (node (ref "U40") (pin "1") (pinfunction "B_1") (pintype "input"))
    )
    (net (code "100") (name "Net-(U41-B)") (class "Default")
      (node (ref "R64") (pin "2") (pinfunction "2_2") (pintype "input"))
      (node (ref "U41") (pin "1") (pinfunction "B_1") (pintype "input"))
    )
    (net (code "101") (name "Net-(U42-B)") (class "Default")
      (node (ref "R65") (pin "2") (pinfunction "2_2") (pintype "input"))
      (node (ref "U42") (pin "1") (pinfunction "B_1") (pintype "input"))
    )
    (net (code "102") (name "Net-(U43-B)") (class "Default")
      (node (ref "R66") (pin "2") (pinfunction "2_2") (pintype "input"))
      (node (ref "U43") (pin "1") (pinfunction "B_1") (pintype "input"))
    )
    (net (code "103") (name "Net-(U44-B)") (class "Default")
      (node (ref "R67") (pin "2") (pinfunction "2_2") (pintype "input"))
      (node (ref "U44") (pin "1") (pinfunction "B_1") (pintype "input"))
    )
    (net (code "104") (name "VIN") (class "Default")
      (node (ref "C6") (pin "2") (pinfunction "2_2") (pintype "input"))
      (node (ref "C8") (pin "2") (pinfunction "2_2") (pintype "input"))
      (node (ref "U1") (pin "1") (pinfunction "1_1") (pintype "unspecified"))
      (node (ref "U45") (pin "3") (pinfunction "VIN_3") (pintype "unspecified"))
      (node (ref "U47") (pin "3") (pinfunction "VIN_3") (pintype "unspecified"))
    )
  )
)
